# SRAM_4MB_2048kbx8_CPLD_v1_2.net
KiCad netlist of a schematic drawn in EAGLE
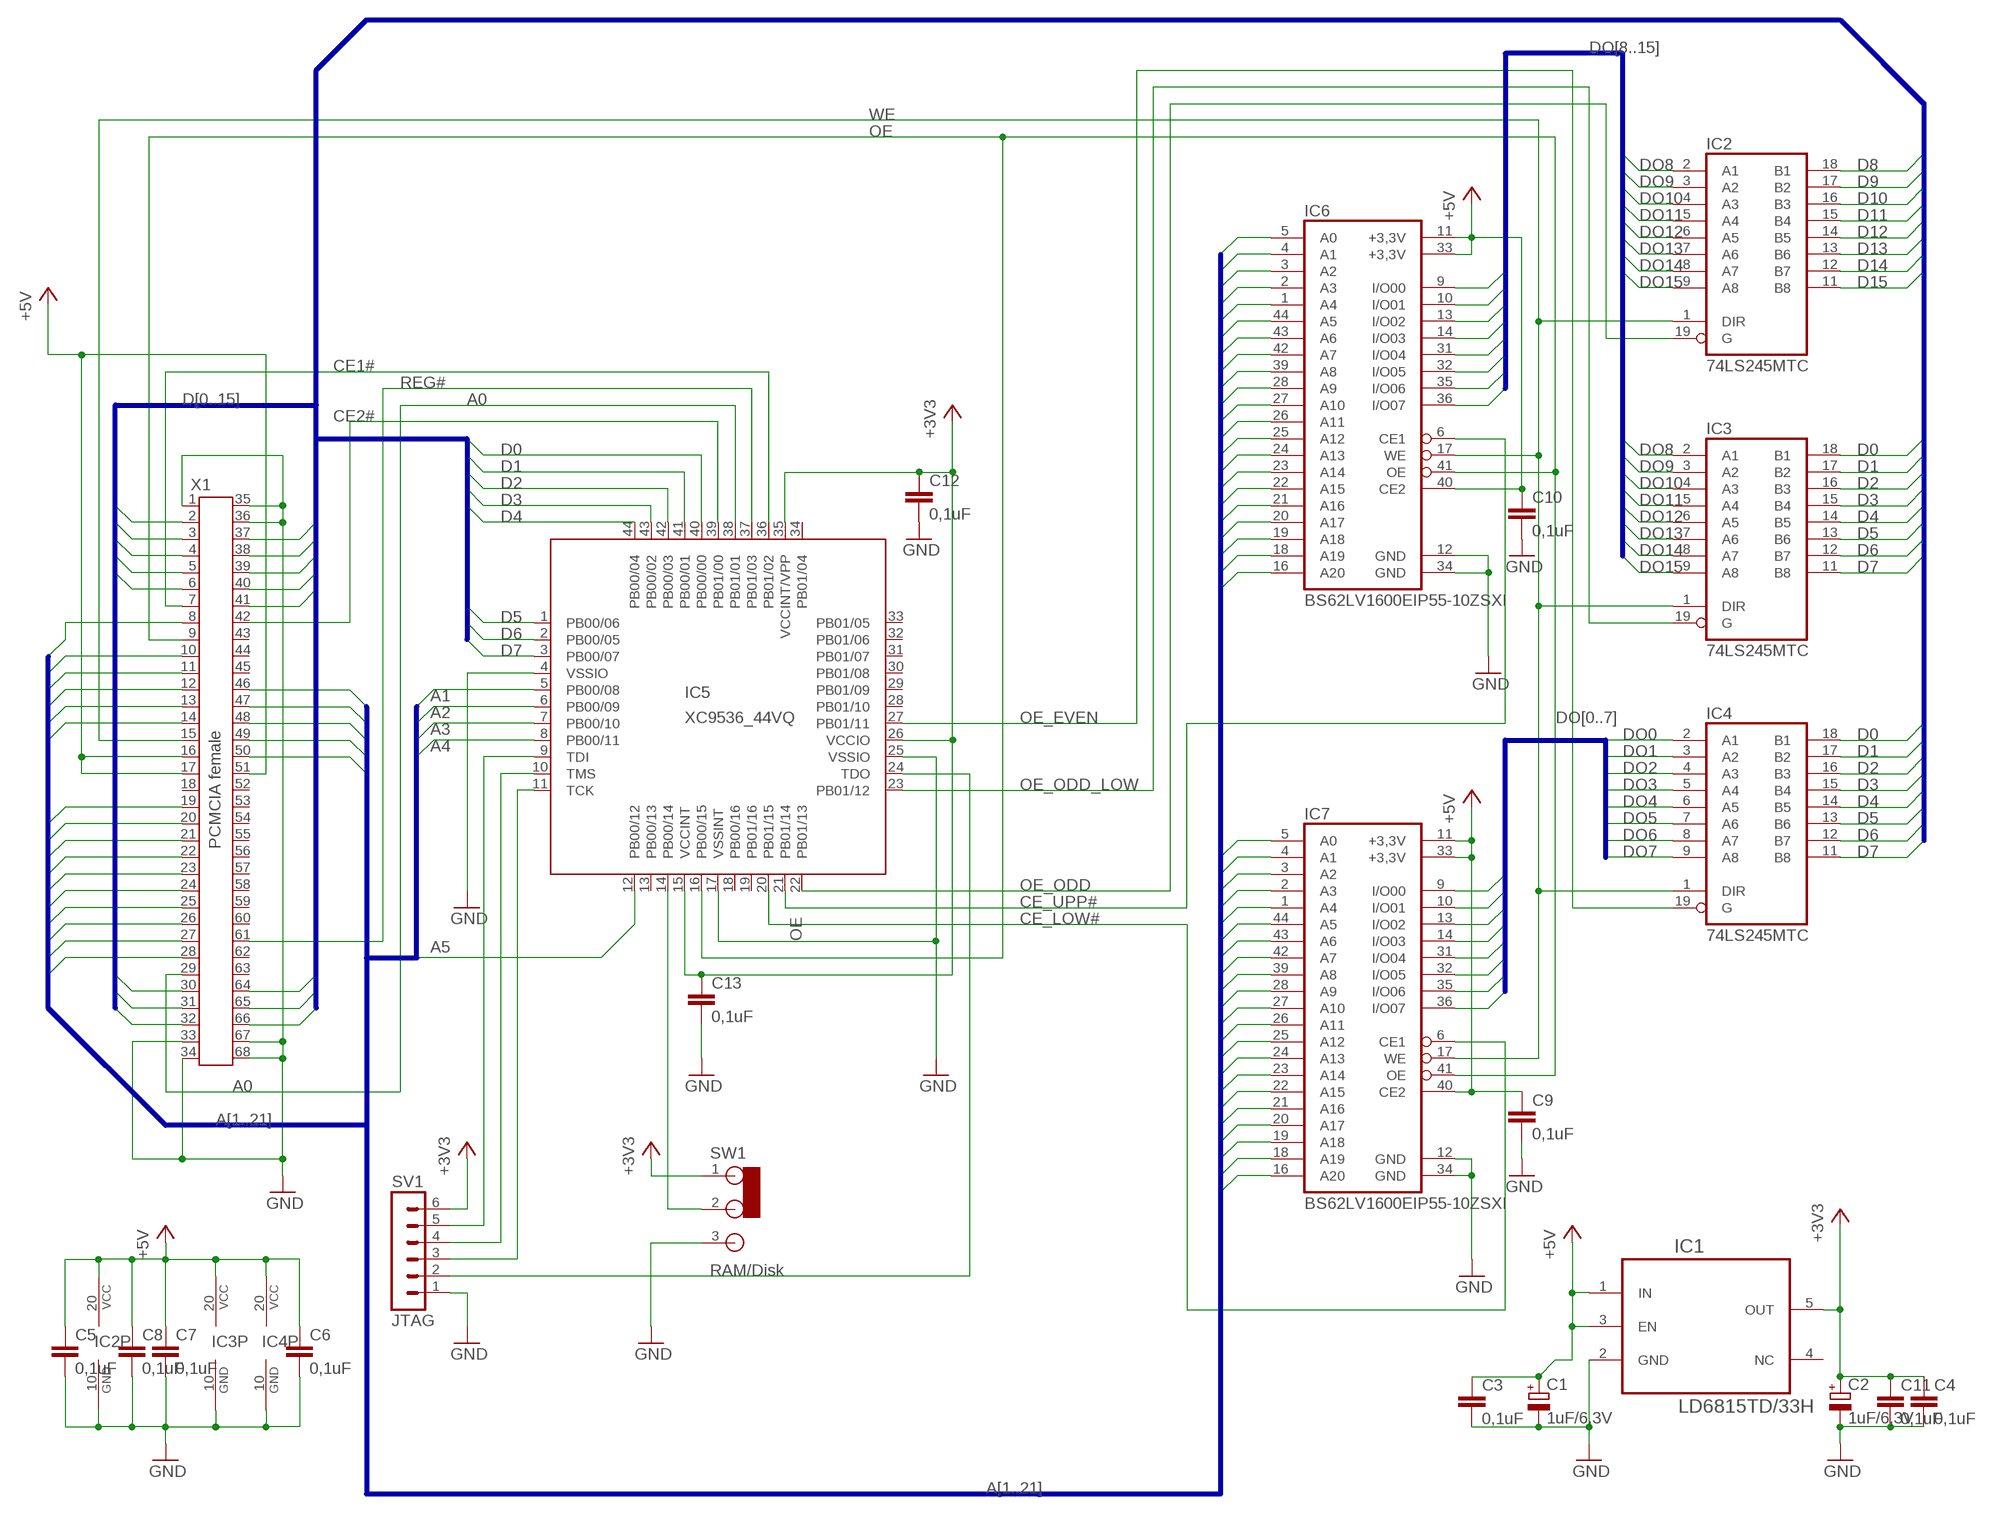
[diagram p0: schematic, sheet 1]

(export (version "E")
  (design (tool "Eeschema 10.0.6"))
  (components
    (comp (ref "C1")
      (value "1uF/6,3V")
      (footprint "eagle-import:A_3216-18R")
      (libsource (lib "eagle-import") (part "CPOL-EUA/3216-18R"))
    )
    (comp (ref "C2")
      (value "1uF/6,3V")
      (footprint "eagle-import:A_3216-18R")
      (libsource (lib "eagle-import") (part "CPOL-EUA/3216-18R"))
    )
    (comp (ref "C3")
      (value "0,1uF")
      (footprint "eagle-import:C0603")
      (libsource (lib "eagle-import") (part "C-EUC0603"))
    )
    (comp (ref "C4")
      (value "0,1uF")
      (footprint "eagle-import:C0603")
      (libsource (lib "eagle-import") (part "C-EUC0603"))
    )
    (comp (ref "C5")
      (value "0,1uF")
      (footprint "eagle-import:C0603")
      (libsource (lib "eagle-import") (part "C-EUC0603"))
    )
    (comp (ref "C6")
      (value "0,1uF")
      (footprint "eagle-import:C0603")
      (libsource (lib "eagle-import") (part "C-EUC0603"))
    )
    (comp (ref "C7")
      (value "0,1uF")
      (footprint "eagle-import:C0603")
      (libsource (lib "eagle-import") (part "C-EUC0603"))
    )
    (comp (ref "C8")
      (value "0,1uF")
      (footprint "eagle-import:C0603")
      (libsource (lib "eagle-import") (part "C-EUC0603"))
    )
    (comp (ref "C9")
      (value "0,1uF")
      (footprint "eagle-import:C0603")
      (libsource (lib "eagle-import") (part "C-EUC0603"))
    )
    (comp (ref "C10")
      (value "0,1uF")
      (footprint "eagle-import:C0603")
      (libsource (lib "eagle-import") (part "C-EUC0603"))
    )
    (comp (ref "C11")
      (value "0,1uF")
      (footprint "eagle-import:C0603")
      (libsource (lib "eagle-import") (part "C-EUC0603"))
    )
    (comp (ref "C12")
      (value "0,1uF")
      (footprint "eagle-import:C0603")
      (libsource (lib "eagle-import") (part "C-EUC0603"))
    )
    (comp (ref "C13")
      (value "0,1uF")
      (footprint "eagle-import:C0603")
      (libsource (lib "eagle-import") (part "C-EUC0603"))
    )
    (comp (ref "IC1")
      (value "LD6815TD/33H")
      (footprint "eagle-import:SOT95P275X110-5N")
      (libsource (lib "eagle-import") (part "LD6815TD/33H"))
    )
    (comp (ref "IC2")
      (value "74LS245MTC")
      (footprint "eagle-import:TSSOP20")
      (libsource (lib "eagle-import") (part "74245MTCLS"))
    )
    (comp (ref "IC3")
      (value "74LS245MTC")
      (footprint "eagle-import:TSSOP20")
      (libsource (lib "eagle-import") (part "74245MTCLS"))
    )
    (comp (ref "IC4")
      (value "74LS245MTC")
      (footprint "eagle-import:TSSOP20")
      (libsource (lib "eagle-import") (part "74245MTCLS"))
    )
    (comp (ref "IC5")
      (value "XC9536_44VQ")
      (footprint "eagle-import:SQFP-S-10X10-44")
      (fields (field (name "MPN") "XC9536-15VQG44C"))
      (libsource (lib "eagle-import") (part "XC9536_44VQ"))
    )
    (comp (ref "IC6")
      (value "BS62LV1600EIP55-10ZSXI")
      (footprint "eagle-import:TSOPII-Z44")
      (libsource (lib "eagle-import") (part "BS62LV1600EIP55-10ZSXI"))
    )
    (comp (ref "IC7")
      (value "BS62LV1600EIP55-10ZSXI")
      (footprint "eagle-import:TSOPII-Z44")
      (libsource (lib "eagle-import") (part "BS62LV1600EIP55-10ZSXI"))
    )
    (comp (ref "SV1")
      (value "JTAG")
      (footprint "eagle-import:MA06-1")
      (libsource (lib "eagle-import") (part "MA06-1"))
    )
    (comp (ref "SW1")
      (value "RAM/Disk")
      (footprint "eagle-import:SWITCH2")
      (libsource (lib "eagle-import") (part "AYZ0102AGRLC"))
    )
    (comp (ref "X1")
      (value "PCMCIA female")
      (footprint "eagle-import:9M681X04")
      (libsource (lib "eagle-import") (part "9M681X03TB9M681Z04"))
    )
  )
  (nets
    (net (code "1") (name "+3V3") (class "Default")
      (node (ref "C11") (pin "1") (pinfunction "1_1") (pintype "passive"))
      (node (ref "C12") (pin "1") (pinfunction "1_1") (pintype "passive"))
      (node (ref "C13") (pin "1") (pinfunction "1_1") (pintype "passive"))
      (node (ref "C2") (pin "+") (pinfunction "+_+") (pintype "passive"))
      (node (ref "C4") (pin "1") (pinfunction "1_1") (pintype "passive"))
      (node (ref "IC1") (pin "5") (pinfunction "OUT_5") (pintype "output"))
      (node (ref "IC5") (pin "15") (pinfunction "VCCINT_15") (pintype "power_in"))
      (node (ref "IC5") (pin "26") (pinfunction "VCCIO_26") (pintype "power_in"))
      (node (ref "IC5") (pin "35") (pinfunction "VCCINT/VPP_35") (pintype "input"))
      (node (ref "SV1") (pin "6") (pinfunction "6_6") (pintype "passive"))
      (node (ref "SW1") (pin "1") (pinfunction "P$1_1") (pintype "bidirectional"))
    )
    (net (code "2") (name "+5V") (class "Default")
      (node (ref "C1") (pin "+") (pinfunction "+_+") (pintype "passive"))
      (node (ref "C10") (pin "1") (pinfunction "1_1") (pintype "passive"))
      (node (ref "C3") (pin "1") (pinfunction "1_1") (pintype "passive"))
      (node (ref "C5") (pin "1") (pinfunction "1_1") (pintype "passive"))
      (node (ref "C6") (pin "1") (pinfunction "1_1") (pintype "passive"))
      (node (ref "C7") (pin "1") (pinfunction "1_1") (pintype "passive"))
      (node (ref "C8") (pin "1") (pinfunction "1_1") (pintype "passive"))
      (node (ref "C9") (pin "1") (pinfunction "1_1") (pintype "passive"))
      (node (ref "IC1") (pin "1") (pinfunction "IN_1") (pintype "input"))
      (node (ref "IC1") (pin "3") (pinfunction "EN_3") (pintype "input"))
      (node (ref "IC2") (pin "20") (pinfunction "VCC_20") (pintype "power_in"))
      (node (ref "IC3") (pin "20") (pinfunction "VCC_20") (pintype "power_in"))
      (node (ref "IC4") (pin "20") (pinfunction "VCC_20") (pintype "power_in"))
      (node (ref "IC6") (pin "11") (pinfunction "+3,3V_11") (pintype "power_in"))
      (node (ref "IC6") (pin "33") (pinfunction "+3,3V_33") (pintype "power_in"))
      (node (ref "IC6") (pin "40") (pinfunction "CE2_40") (pintype "input"))
      (node (ref "IC7") (pin "11") (pinfunction "+3,3V_11") (pintype "power_in"))
      (node (ref "IC7") (pin "33") (pinfunction "+3,3V_33") (pintype "power_in"))
      (node (ref "IC7") (pin "40") (pinfunction "CE2_40") (pintype "input"))
      (node (ref "X1") (pin "16") (pinfunction "16_16") (pintype "passive"))
      (node (ref "X1") (pin "17") (pinfunction "17_17") (pintype "passive"))
      (node (ref "X1") (pin "51") (pinfunction "51_51") (pintype "passive"))
    )
    (net (code "3") (name "/A0") (class "Default")
      (node (ref "IC5") (pin "38") (pinfunction "PB01/01_38") (pintype "bidirectional"))
      (node (ref "X1") (pin "29") (pinfunction "29_29") (pintype "passive"))
    )
    (net (code "4") (name "/A1") (class "Default")
      (node (ref "IC5") (pin "5") (pinfunction "PB00/08_5") (pintype "bidirectional"))
      (node (ref "IC6") (pin "5") (pinfunction "A0_5") (pintype "input"))
      (node (ref "IC7") (pin "5") (pinfunction "A0_5") (pintype "input"))
      (node (ref "X1") (pin "28") (pinfunction "28_28") (pintype "passive"))
    )
    (net (code "5") (name "/A2") (class "Default")
      (node (ref "IC5") (pin "6") (pinfunction "PB00/09_6") (pintype "bidirectional"))
      (node (ref "IC6") (pin "4") (pinfunction "A1_4") (pintype "input"))
      (node (ref "IC7") (pin "4") (pinfunction "A1_4") (pintype "input"))
      (node (ref "X1") (pin "27") (pinfunction "27_27") (pintype "passive"))
    )
    (net (code "6") (name "/A3") (class "Default")
      (node (ref "IC5") (pin "7") (pinfunction "PB00/10_7") (pintype "bidirectional"))
      (node (ref "IC6") (pin "3") (pinfunction "A2_3") (pintype "input"))
      (node (ref "IC7") (pin "3") (pinfunction "A2_3") (pintype "input"))
      (node (ref "X1") (pin "26") (pinfunction "26_26") (pintype "passive"))
    )
    (net (code "7") (name "/A4") (class "Default")
      (node (ref "IC5") (pin "8") (pinfunction "PB00/11_8") (pintype "bidirectional"))
      (node (ref "IC6") (pin "2") (pinfunction "A3_2") (pintype "input"))
      (node (ref "IC7") (pin "2") (pinfunction "A3_2") (pintype "input"))
      (node (ref "X1") (pin "25") (pinfunction "25_25") (pintype "passive"))
    )
    (net (code "8") (name "/A5") (class "Default")
      (node (ref "IC5") (pin "12") (pinfunction "PB00/12_12") (pintype "bidirectional"))
      (node (ref "IC6") (pin "1") (pinfunction "A4_1") (pintype "input"))
      (node (ref "IC7") (pin "1") (pinfunction "A4_1") (pintype "input"))
      (node (ref "X1") (pin "24") (pinfunction "24_24") (pintype "passive"))
    )
    (net (code "9") (name "/A6") (class "Default")
      (node (ref "IC6") (pin "44") (pinfunction "A5_44") (pintype "input"))
      (node (ref "IC7") (pin "44") (pinfunction "A5_44") (pintype "input"))
      (node (ref "X1") (pin "23") (pinfunction "23_23") (pintype "passive"))
    )
    (net (code "10") (name "/A7") (class "Default")
      (node (ref "IC6") (pin "43") (pinfunction "A6_43") (pintype "input"))
      (node (ref "IC7") (pin "43") (pinfunction "A6_43") (pintype "input"))
      (node (ref "X1") (pin "22") (pinfunction "22_22") (pintype "passive"))
    )
    (net (code "11") (name "/A8") (class "Default")
      (node (ref "IC6") (pin "42") (pinfunction "A7_42") (pintype "input"))
      (node (ref "IC7") (pin "42") (pinfunction "A7_42") (pintype "input"))
      (node (ref "X1") (pin "12") (pinfunction "12_12") (pintype "passive"))
    )
    (net (code "12") (name "/A9") (class "Default")
      (node (ref "IC6") (pin "39") (pinfunction "A8_39") (pintype "input"))
      (node (ref "IC7") (pin "39") (pinfunction "A8_39") (pintype "input"))
      (node (ref "X1") (pin "11") (pinfunction "11_11") (pintype "passive"))
    )
    (net (code "13") (name "/A10") (class "Default")
      (node (ref "IC6") (pin "28") (pinfunction "A9_28") (pintype "input"))
      (node (ref "IC7") (pin "28") (pinfunction "A9_28") (pintype "input"))
      (node (ref "X1") (pin "8") (pinfunction "8_8") (pintype "passive"))
    )
    (net (code "14") (name "/A11") (class "Default")
      (node (ref "IC6") (pin "27") (pinfunction "A10_27") (pintype "input"))
      (node (ref "IC7") (pin "27") (pinfunction "A10_27") (pintype "input"))
      (node (ref "X1") (pin "10") (pinfunction "10_10") (pintype "passive"))
    )
    (net (code "15") (name "/A12") (class "Default")
      (node (ref "IC6") (pin "26") (pinfunction "A11_26") (pintype "input"))
      (node (ref "IC7") (pin "26") (pinfunction "A11_26") (pintype "input"))
      (node (ref "X1") (pin "21") (pinfunction "21_21") (pintype "passive"))
    )
    (net (code "16") (name "/A13") (class "Default")
      (node (ref "IC6") (pin "25") (pinfunction "A12_25") (pintype "input"))
      (node (ref "IC7") (pin "25") (pinfunction "A12_25") (pintype "input"))
      (node (ref "X1") (pin "13") (pinfunction "13_13") (pintype "passive"))
    )
    (net (code "17") (name "/A14") (class "Default")
      (node (ref "IC6") (pin "24") (pinfunction "A13_24") (pintype "input"))
      (node (ref "IC7") (pin "24") (pinfunction "A13_24") (pintype "input"))
      (node (ref "X1") (pin "14") (pinfunction "14_14") (pintype "passive"))
    )
    (net (code "18") (name "/A15") (class "Default")
      (node (ref "IC6") (pin "23") (pinfunction "A14_23") (pintype "input"))
      (node (ref "IC7") (pin "23") (pinfunction "A14_23") (pintype "input"))
      (node (ref "X1") (pin "20") (pinfunction "20_20") (pintype "passive"))
    )
    (net (code "19") (name "/A16") (class "Default")
      (node (ref "IC6") (pin "22") (pinfunction "A15_22") (pintype "input"))
      (node (ref "IC7") (pin "22") (pinfunction "A15_22") (pintype "input"))
      (node (ref "X1") (pin "19") (pinfunction "19_19") (pintype "passive"))
    )
    (net (code "20") (name "/A17") (class "Default")
      (node (ref "IC6") (pin "21") (pinfunction "A16_21") (pintype "input"))
      (node (ref "IC7") (pin "21") (pinfunction "A16_21") (pintype "input"))
      (node (ref "X1") (pin "46") (pinfunction "46_46") (pintype "passive"))
    )
    (net (code "21") (name "/A18") (class "Default")
      (node (ref "IC6") (pin "20") (pinfunction "A17_20") (pintype "input"))
      (node (ref "IC7") (pin "20") (pinfunction "A17_20") (pintype "input"))
      (node (ref "X1") (pin "47") (pinfunction "47_47") (pintype "passive"))
    )
    (net (code "22") (name "/A19") (class "Default")
      (node (ref "IC6") (pin "19") (pinfunction "A18_19") (pintype "input"))
      (node (ref "IC7") (pin "19") (pinfunction "A18_19") (pintype "input"))
      (node (ref "X1") (pin "48") (pinfunction "48_48") (pintype "passive"))
    )
    (net (code "23") (name "/A20") (class "Default")
      (node (ref "IC6") (pin "18") (pinfunction "A19_18") (pintype "input"))
      (node (ref "IC7") (pin "18") (pinfunction "A19_18") (pintype "input"))
      (node (ref "X1") (pin "49") (pinfunction "49_49") (pintype "passive"))
    )
    (net (code "24") (name "/A21") (class "Default")
      (node (ref "IC6") (pin "16") (pinfunction "A20_16") (pintype "input"))
      (node (ref "IC7") (pin "16") (pinfunction "A20_16") (pintype "input"))
      (node (ref "X1") (pin "50") (pinfunction "50_50") (pintype "passive"))
    )
    (net (code "26") (name "/CE1#") (class "Default")
      (node (ref "IC5") (pin "36") (pinfunction "PB01/02_36") (pintype "bidirectional"))
      (node (ref "X1") (pin "7") (pinfunction "7_7") (pintype "passive"))
    )
    (net (code "27") (name "/CE2#") (class "Default")
      (node (ref "IC5") (pin "39") (pinfunction "PB01/00_39") (pintype "bidirectional"))
      (node (ref "X1") (pin "42") (pinfunction "42_42") (pintype "passive"))
    )
    (net (code "28") (name "/CE_LOW#") (class "Default")
      (node (ref "IC5") (pin "20") (pinfunction "PB01/15_20") (pintype "bidirectional"))
      (node (ref "IC7") (pin "6") (pinfunction "CE1_6") (pintype "input"))
    )
    (net (code "29") (name "/CE_UPP#") (class "Default")
      (node (ref "IC5") (pin "21") (pinfunction "PB01/14_21") (pintype "bidirectional"))
      (node (ref "IC6") (pin "6") (pinfunction "CE1_6") (pintype "input"))
    )
    (net (code "30") (name "/D0") (class "Default")
      (node (ref "IC3") (pin "18") (pinfunction "B1_18") (pintype "bidirectional"))
      (node (ref "IC4") (pin "18") (pinfunction "B1_18") (pintype "bidirectional"))
      (node (ref "IC5") (pin "40") (pinfunction "PB00/00_40") (pintype "bidirectional"))
      (node (ref "X1") (pin "30") (pinfunction "30_30") (pintype "passive"))
    )
    (net (code "31") (name "/D1") (class "Default")
      (node (ref "IC3") (pin "17") (pinfunction "B2_17") (pintype "bidirectional"))
      (node (ref "IC4") (pin "17") (pinfunction "B2_17") (pintype "bidirectional"))
      (node (ref "IC5") (pin "41") (pinfunction "PB00/01_41") (pintype "bidirectional"))
      (node (ref "X1") (pin "31") (pinfunction "31_31") (pintype "passive"))
    )
    (net (code "32") (name "/D2") (class "Default")
      (node (ref "IC3") (pin "16") (pinfunction "B3_16") (pintype "bidirectional"))
      (node (ref "IC4") (pin "16") (pinfunction "B3_16") (pintype "bidirectional"))
      (node (ref "IC5") (pin "42") (pinfunction "PB00/03_42") (pintype "bidirectional"))
      (node (ref "X1") (pin "32") (pinfunction "32_32") (pintype "passive"))
    )
    (net (code "33") (name "/D3") (class "Default")
      (node (ref "IC3") (pin "15") (pinfunction "B4_15") (pintype "bidirectional"))
      (node (ref "IC4") (pin "15") (pinfunction "B4_15") (pintype "bidirectional"))
      (node (ref "IC5") (pin "43") (pinfunction "PB00/02_43") (pintype "bidirectional"))
      (node (ref "X1") (pin "2") (pinfunction "2_2") (pintype "passive"))
    )
    (net (code "34") (name "/D4") (class "Default")
      (node (ref "IC3") (pin "14") (pinfunction "B5_14") (pintype "bidirectional"))
      (node (ref "IC4") (pin "14") (pinfunction "B5_14") (pintype "bidirectional"))
      (node (ref "IC5") (pin "44") (pinfunction "PB00/04_44") (pintype "bidirectional"))
      (node (ref "X1") (pin "3") (pinfunction "3_3") (pintype "passive"))
    )
    (net (code "35") (name "/D5") (class "Default")
      (node (ref "IC3") (pin "13") (pinfunction "B6_13") (pintype "bidirectional"))
      (node (ref "IC4") (pin "13") (pinfunction "B6_13") (pintype "bidirectional"))
      (node (ref "IC5") (pin "1") (pinfunction "PB00/06_1") (pintype "bidirectional"))
      (node (ref "X1") (pin "4") (pinfunction "4_4") (pintype "passive"))
    )
    (net (code "36") (name "/D6") (class "Default")
      (node (ref "IC3") (pin "12") (pinfunction "B7_12") (pintype "bidirectional"))
      (node (ref "IC4") (pin "12") (pinfunction "B7_12") (pintype "bidirectional"))
      (node (ref "IC5") (pin "2") (pinfunction "PB00/05_2") (pintype "bidirectional"))
      (node (ref "X1") (pin "5") (pinfunction "5_5") (pintype "passive"))
    )
    (net (code "37") (name "/D7") (class "Default")
      (node (ref "IC3") (pin "11") (pinfunction "B8_11") (pintype "bidirectional"))
      (node (ref "IC4") (pin "11") (pinfunction "B8_11") (pintype "bidirectional"))
      (node (ref "IC5") (pin "3") (pinfunction "PB00/07_3") (pintype "bidirectional"))
      (node (ref "X1") (pin "6") (pinfunction "6_6") (pintype "passive"))
    )
    (net (code "38") (name "/D8") (class "Default")
      (node (ref "IC2") (pin "18") (pinfunction "B1_18") (pintype "bidirectional"))
      (node (ref "X1") (pin "64") (pinfunction "64_64") (pintype "passive"))
    )
    (net (code "39") (name "/D9") (class "Default")
      (node (ref "IC2") (pin "17") (pinfunction "B2_17") (pintype "bidirectional"))
      (node (ref "X1") (pin "65") (pinfunction "65_65") (pintype "passive"))
    )
    (net (code "40") (name "/D10") (class "Default")
      (node (ref "IC2") (pin "16") (pinfunction "B3_16") (pintype "bidirectional"))
      (node (ref "X1") (pin "66") (pinfunction "66_66") (pintype "passive"))
    )
    (net (code "41") (name "/D11") (class "Default")
      (node (ref "IC2") (pin "15") (pinfunction "B4_15") (pintype "bidirectional"))
      (node (ref "X1") (pin "37") (pinfunction "37_37") (pintype "passive"))
    )
    (net (code "42") (name "/D12") (class "Default")
      (node (ref "IC2") (pin "14") (pinfunction "B5_14") (pintype "bidirectional"))
      (node (ref "X1") (pin "38") (pinfunction "38_38") (pintype "passive"))
    )
    (net (code "43") (name "/D13") (class "Default")
      (node (ref "IC2") (pin "13") (pinfunction "B6_13") (pintype "bidirectional"))
      (node (ref "X1") (pin "39") (pinfunction "39_39") (pintype "passive"))
    )
    (net (code "44") (name "/D14") (class "Default")
      (node (ref "IC2") (pin "12") (pinfunction "B7_12") (pintype "bidirectional"))
      (node (ref "X1") (pin "40") (pinfunction "40_40") (pintype "passive"))
    )
    (net (code "45") (name "/D15") (class "Default")
      (node (ref "IC2") (pin "11") (pinfunction "B8_11") (pintype "bidirectional"))
      (node (ref "X1") (pin "41") (pinfunction "41_41") (pintype "passive"))
    )
    (net (code "46") (name "/DO0") (class "Default")
      (node (ref "IC4") (pin "2") (pinfunction "A1_2") (pintype "bidirectional"))
      (node (ref "IC7") (pin "9") (pinfunction "I/O00_9") (pintype "bidirectional"))
    )
    (net (code "47") (name "/DO1") (class "Default")
      (node (ref "IC4") (pin "3") (pinfunction "A2_3") (pintype "bidirectional"))
      (node (ref "IC7") (pin "10") (pinfunction "I/O01_10") (pintype "bidirectional"))
    )
    (net (code "48") (name "/DO2") (class "Default")
      (node (ref "IC4") (pin "4") (pinfunction "A3_4") (pintype "bidirectional"))
      (node (ref "IC7") (pin "13") (pinfunction "I/O02_13") (pintype "bidirectional"))
    )
    (net (code "49") (name "/DO3") (class "Default")
      (node (ref "IC4") (pin "5") (pinfunction "A4_5") (pintype "bidirectional"))
      (node (ref "IC7") (pin "14") (pinfunction "I/O03_14") (pintype "bidirectional"))
    )
    (net (code "50") (name "/DO4") (class "Default")
      (node (ref "IC4") (pin "6") (pinfunction "A5_6") (pintype "bidirectional"))
      (node (ref "IC7") (pin "31") (pinfunction "I/O04_31") (pintype "bidirectional"))
    )
    (net (code "51") (name "/DO5") (class "Default")
      (node (ref "IC4") (pin "7") (pinfunction "A6_7") (pintype "bidirectional"))
      (node (ref "IC7") (pin "32") (pinfunction "I/O05_32") (pintype "bidirectional"))
    )
    (net (code "52") (name "/DO6") (class "Default")
      (node (ref "IC4") (pin "8") (pinfunction "A7_8") (pintype "bidirectional"))
      (node (ref "IC7") (pin "35") (pinfunction "I/O06_35") (pintype "bidirectional"))
    )
    (net (code "53") (name "/DO7") (class "Default")
      (node (ref "IC4") (pin "9") (pinfunction "A8_9") (pintype "bidirectional"))
      (node (ref "IC7") (pin "36") (pinfunction "I/O07_36") (pintype "bidirectional"))
    )
    (net (code "54") (name "/DO8") (class "Default")
      (node (ref "IC2") (pin "2") (pinfunction "A1_2") (pintype "bidirectional"))
      (node (ref "IC3") (pin "2") (pinfunction "A1_2") (pintype "bidirectional"))
      (node (ref "IC6") (pin "9") (pinfunction "I/O00_9") (pintype "bidirectional"))
    )
    (net (code "55") (name "/DO9") (class "Default")
      (node (ref "IC2") (pin "3") (pinfunction "A2_3") (pintype "bidirectional"))
      (node (ref "IC3") (pin "3") (pinfunction "A2_3") (pintype "bidirectional"))
      (node (ref "IC6") (pin "10") (pinfunction "I/O01_10") (pintype "bidirectional"))
    )
    (net (code "56") (name "/DO10") (class "Default")
      (node (ref "IC2") (pin "4") (pinfunction "A3_4") (pintype "bidirectional"))
      (node (ref "IC3") (pin "4") (pinfunction "A3_4") (pintype "bidirectional"))
      (node (ref "IC6") (pin "13") (pinfunction "I/O02_13") (pintype "bidirectional"))
    )
    (net (code "57") (name "/DO11") (class "Default")
      (node (ref "IC2") (pin "5") (pinfunction "A4_5") (pintype "bidirectional"))
      (node (ref "IC3") (pin "5") (pinfunction "A4_5") (pintype "bidirectional"))
      (node (ref "IC6") (pin "14") (pinfunction "I/O03_14") (pintype "bidirectional"))
    )
    (net (code "58") (name "/DO12") (class "Default")
      (node (ref "IC2") (pin "6") (pinfunction "A5_6") (pintype "bidirectional"))
      (node (ref "IC3") (pin "6") (pinfunction "A5_6") (pintype "bidirectional"))
      (node (ref "IC6") (pin "31") (pinfunction "I/O04_31") (pintype "bidirectional"))
    )
    (net (code "59") (name "/DO13") (class "Default")
      (node (ref "IC2") (pin "7") (pinfunction "A6_7") (pintype "bidirectional"))
      (node (ref "IC3") (pin "7") (pinfunction "A6_7") (pintype "bidirectional"))
      (node (ref "IC6") (pin "32") (pinfunction "I/O05_32") (pintype "bidirectional"))
    )
    (net (code "60") (name "/DO14") (class "Default")
      (node (ref "IC2") (pin "8") (pinfunction "A7_8") (pintype "bidirectional"))
      (node (ref "IC3") (pin "8") (pinfunction "A7_8") (pintype "bidirectional"))
      (node (ref "IC6") (pin "35") (pinfunction "I/O06_35") (pintype "bidirectional"))
    )
    (net (code "61") (name "/DO15") (class "Default")
      (node (ref "IC2") (pin "9") (pinfunction "A8_9") (pintype "bidirectional"))
      (node (ref "IC3") (pin "9") (pinfunction "A8_9") (pintype "bidirectional"))
      (node (ref "IC6") (pin "36") (pinfunction "I/O07_36") (pintype "bidirectional"))
    )
    (net (code "65") (name "/OE") (class "Default")
      (node (ref "IC5") (pin "16") (pinfunction "PB00/15_16") (pintype "bidirectional"))
      (node (ref "IC6") (pin "41") (pinfunction "OE_41") (pintype "input"))
      (node (ref "IC7") (pin "41") (pinfunction "OE_41") (pintype "input"))
      (node (ref "X1") (pin "9") (pinfunction "9_9") (pintype "passive"))
    )
    (net (code "66") (name "/OE_EVEN") (class "Default")
      (node (ref "IC4") (pin "19") (pinfunction "G_19") (pintype "input"))
      (node (ref "IC5") (pin "27") (pinfunction "PB01/11_27") (pintype "bidirectional"))
    )
    (net (code "67") (name "/OE_ODD") (class "Default")
      (node (ref "IC2") (pin "19") (pinfunction "G_19") (pintype "input"))
      (node (ref "IC5") (pin "22") (pinfunction "PB01/13_22") (pintype "bidirectional"))
    )
    (net (code "68") (name "/OE_ODD_LOW") (class "Default")
      (node (ref "IC3") (pin "19") (pinfunction "G_19") (pintype "input"))
      (node (ref "IC5") (pin "23") (pinfunction "PB01/12_23") (pintype "bidirectional"))
    )
    (net (code "69") (name "/REG#") (class "Default")
      (node (ref "IC5") (pin "37") (pinfunction "PB01/03_37") (pintype "bidirectional"))
      (node (ref "X1") (pin "61") (pinfunction "61_61") (pintype "passive"))
    )
    (net (code "70") (name "/WE") (class "Default")
      (node (ref "IC2") (pin "1") (pinfunction "DIR_1") (pintype "input"))
      (node (ref "IC3") (pin "1") (pinfunction "DIR_1") (pintype "input"))
      (node (ref "IC4") (pin "1") (pinfunction "DIR_1") (pintype "input"))
      (node (ref "IC6") (pin "17") (pinfunction "WE_17") (pintype "input"))
      (node (ref "IC7") (pin "17") (pinfunction "WE_17") (pintype "input"))
      (node (ref "X1") (pin "15") (pinfunction "15_15") (pintype "passive"))
    )
    (net (code "71") (name "GND") (class "Default")
      (node (ref "C1") (pin "-") (pinfunction "-_-") (pintype "passive"))
      (node (ref "C10") (pin "2") (pinfunction "2_2") (pintype "passive"))
      (node (ref "C11") (pin "2") (pinfunction "2_2") (pintype "passive"))
      (node (ref "C12") (pin "2") (pinfunction "2_2") (pintype "passive"))
      (node (ref "C13") (pin "2") (pinfunction "2_2") (pintype "passive"))
      (node (ref "C2") (pin "-") (pinfunction "-_-") (pintype "passive"))
      (node (ref "C3") (pin "2") (pinfunction "2_2") (pintype "passive"))
      (node (ref "C4") (pin "2") (pinfunction "2_2") (pintype "passive"))
      (node (ref "C5") (pin "2") (pinfunction "2_2") (pintype "passive"))
      (node (ref "C6") (pin "2") (pinfunction "2_2") (pintype "passive"))
      (node (ref "C7") (pin "2") (pinfunction "2_2") (pintype "passive"))
      (node (ref "C8") (pin "2") (pinfunction "2_2") (pintype "passive"))
      (node (ref "C9") (pin "2") (pinfunction "2_2") (pintype "passive"))
      (node (ref "IC1") (pin "2") (pinfunction "GND_2") (pintype "passive"))
      (node (ref "IC2") (pin "10") (pinfunction "GND_10") (pintype "power_in"))
      (node (ref "IC3") (pin "10") (pinfunction "GND_10") (pintype "power_in"))
      (node (ref "IC4") (pin "10") (pinfunction "GND_10") (pintype "power_in"))
      (node (ref "IC5") (pin "17") (pinfunction "VSSINT_17") (pintype "power_in"))
      (node (ref "IC5") (pin "25") (pinfunction "VSSIO_25") (pintype "power_in"))
      (node (ref "IC5") (pin "4") (pinfunction "VSSIO_4") (pintype "power_in"))
      (node (ref "IC6") (pin "12") (pinfunction "GND_12") (pintype "power_in"))
      (node (ref "IC6") (pin "34") (pinfunction "GND_34") (pintype "power_in"))
      (node (ref "IC7") (pin "12") (pinfunction "GND_12") (pintype "power_in"))
      (node (ref "IC7") (pin "34") (pinfunction "GND_34") (pintype "power_in"))
      (node (ref "SV1") (pin "1") (pinfunction "1_1") (pintype "passive"))
      (node (ref "SW1") (pin "3") (pinfunction "P$3_3") (pintype "bidirectional"))
      (node (ref "X1") (pin "1") (pinfunction "1_1") (pintype "passive"))
      (node (ref "X1") (pin "33") (pinfunction "33_33") (pintype "passive"))
      (node (ref "X1") (pin "34") (pinfunction "34_34") (pintype "passive"))
      (node (ref "X1") (pin "35") (pinfunction "35_35") (pintype "passive"))
      (node (ref "X1") (pin "36") (pinfunction "36_36") (pintype "passive"))
      (node (ref "X1") (pin "67") (pinfunction "67_67") (pintype "passive"))
      (node (ref "X1") (pin "68") (pinfunction "68_68") (pintype "passive"))
    )
    (net (code "72") (name "Net-(IC5-PB00{slash}14)") (class "Default")
      (node (ref "IC5") (pin "14") (pinfunction "PB00/14_14") (pintype "bidirectional"))
      (node (ref "SW1") (pin "2") (pinfunction "P$2_2") (pintype "bidirectional"))
    )
    (net (code "73") (name "Net-(IC5-TCK)") (class "Default")
      (node (ref "IC5") (pin "11") (pinfunction "TCK_11") (pintype "input"))
      (node (ref "SV1") (pin "3") (pinfunction "3_3") (pintype "passive"))
    )
    (net (code "74") (name "Net-(IC5-TDI)") (class "Default")
      (node (ref "IC5") (pin "9") (pinfunction "TDI_9") (pintype "input"))
      (node (ref "SV1") (pin "5") (pinfunction "5_5") (pintype "passive"))
    )
    (net (code "75") (name "Net-(IC5-TDO)") (class "Default")
      (node (ref "IC5") (pin "24") (pinfunction "TDO_24") (pintype "output"))
      (node (ref "SV1") (pin "2") (pinfunction "2_2") (pintype "passive"))
    )
    (net (code "76") (name "Net-(IC5-TMS)") (class "Default")
      (node (ref "IC5") (pin "10") (pinfunction "TMS_10") (pintype "input"))
      (node (ref "SV1") (pin "4") (pinfunction "4_4") (pintype "passive"))
    )
    (net (code "77") (name "unconnected-(IC1-NC-Pad4)") (class "Default")
      (node (ref "IC1") (pin "4") (pinfunction "NC_4") (pintype "no_connect"))
    )
    (net (code "78") (name "unconnected-(IC5-PB00{slash}13-Pad13)") (class "Default")
      (node (ref "IC5") (pin "13") (pinfunction "PB00/13_13") (pintype "bidirectional"))
    )
    (net (code "79") (name "unconnected-(IC5-PB00{slash}16-Pad18)") (class "Default")
      (node (ref "IC5") (pin "18") (pinfunction "PB00/16_18") (pintype "bidirectional"))
    )
    (net (code "80") (name "unconnected-(IC5-PB01{slash}04-Pad34)") (class "Default")
      (node (ref "IC5") (pin "34") (pinfunction "PB01/04_34") (pintype "bidirectional"))
    )
    (net (code "81") (name "unconnected-(IC5-PB01{slash}05-Pad33)") (class "Default")
      (node (ref "IC5") (pin "33") (pinfunction "PB01/05_33") (pintype "bidirectional"))
    )
    (net (code "82") (name "unconnected-(IC5-PB01{slash}06-Pad32)") (class "Default")
      (node (ref "IC5") (pin "32") (pinfunction "PB01/06_32") (pintype "bidirectional"))
    )
    (net (code "83") (name "unconnected-(IC5-PB01{slash}07-Pad31)") (class "Default")
      (node (ref "IC5") (pin "31") (pinfunction "PB01/07_31") (pintype "bidirectional"))
    )
    (net (code "84") (name "unconnected-(IC5-PB01{slash}08-Pad30)") (class "Default")
      (node (ref "IC5") (pin "30") (pinfunction "PB01/08_30") (pintype "bidirectional"))
    )
    (net (code "85") (name "unconnected-(IC5-PB01{slash}09-Pad29)") (class "Default")
      (node (ref "IC5") (pin "29") (pinfunction "PB01/09_29") (pintype "bidirectional"))
    )
    (net (code "86") (name "unconnected-(IC5-PB01{slash}10-Pad28)") (class "Default")
      (node (ref "IC5") (pin "28") (pinfunction "PB01/10_28") (pintype "bidirectional"))
    )
    (net (code "87") (name "unconnected-(IC5-PB01{slash}16-Pad19)") (class "Default")
      (node (ref "IC5") (pin "19") (pinfunction "PB01/16_19") (pintype "bidirectional"))
    )
    (net (code "88") (name "unconnected-(X1-Pad18)") (class "Default")
      (node (ref "X1") (pin "18") (pinfunction "18_18") (pintype "passive"))
    )
    (net (code "89") (name "unconnected-(X1-Pad43)") (class "Default")
      (node (ref "X1") (pin "43") (pinfunction "43_43") (pintype "passive"))
    )
    (net (code "90") (name "unconnected-(X1-Pad44)") (class "Default")
      (node (ref "X1") (pin "44") (pinfunction "44_44") (pintype "passive"))
    )
    (net (code "91") (name "unconnected-(X1-Pad45)") (class "Default")
      (node (ref "X1") (pin "45") (pinfunction "45_45") (pintype "passive"))
    )
    (net (code "92") (name "unconnected-(X1-Pad52)") (class "Default")
      (node (ref "X1") (pin "52") (pinfunction "52_52") (pintype "passive"))
    )
    (net (code "93") (name "unconnected-(X1-Pad53)") (class "Default")
      (node (ref "X1") (pin "53") (pinfunction "53_53") (pintype "passive"))
    )
    (net (code "94") (name "unconnected-(X1-Pad54)") (class "Default")
      (node (ref "X1") (pin "54") (pinfunction "54_54") (pintype "passive"))
    )
    (net (code "95") (name "unconnected-(X1-Pad55)") (class "Default")
      (node (ref "X1") (pin "55") (pinfunction "55_55") (pintype "passive"))
    )
    (net (code "96") (name "unconnected-(X1-Pad56)") (class "Default")
      (node (ref "X1") (pin "56") (pinfunction "56_56") (pintype "passive"))
    )
    (net (code "97") (name "unconnected-(X1-Pad57)") (class "Default")
      (node (ref "X1") (pin "57") (pinfunction "57_57") (pintype "passive"))
    )
    (net (code "98") (name "unconnected-(X1-Pad58)") (class "Default")
      (node (ref "X1") (pin "58") (pinfunction "58_58") (pintype "passive"))
    )
    (net (code "99") (name "unconnected-(X1-Pad59)") (class "Default")
      (node (ref "X1") (pin "59") (pinfunction "59_59") (pintype "passive"))
    )
    (net (code "100") (name "unconnected-(X1-Pad60)") (class "Default")
      (node (ref "X1") (pin "60") (pinfunction "60_60") (pintype "passive"))
    )
    (net (code "101") (name "unconnected-(X1-Pad62)") (class "Default")
      (node (ref "X1") (pin "62") (pinfunction "62_62") (pintype "passive"))
    )
    (net (code "102") (name "unconnected-(X1-Pad63)") (class "Default")
      (node (ref "X1") (pin "63") (pinfunction "63_63") (pintype "passive"))
    )
  )
)
